# RCJ_OnStage2024_FC_pwr.net
KiCad netlist of a schematic drawn in Altium Designer
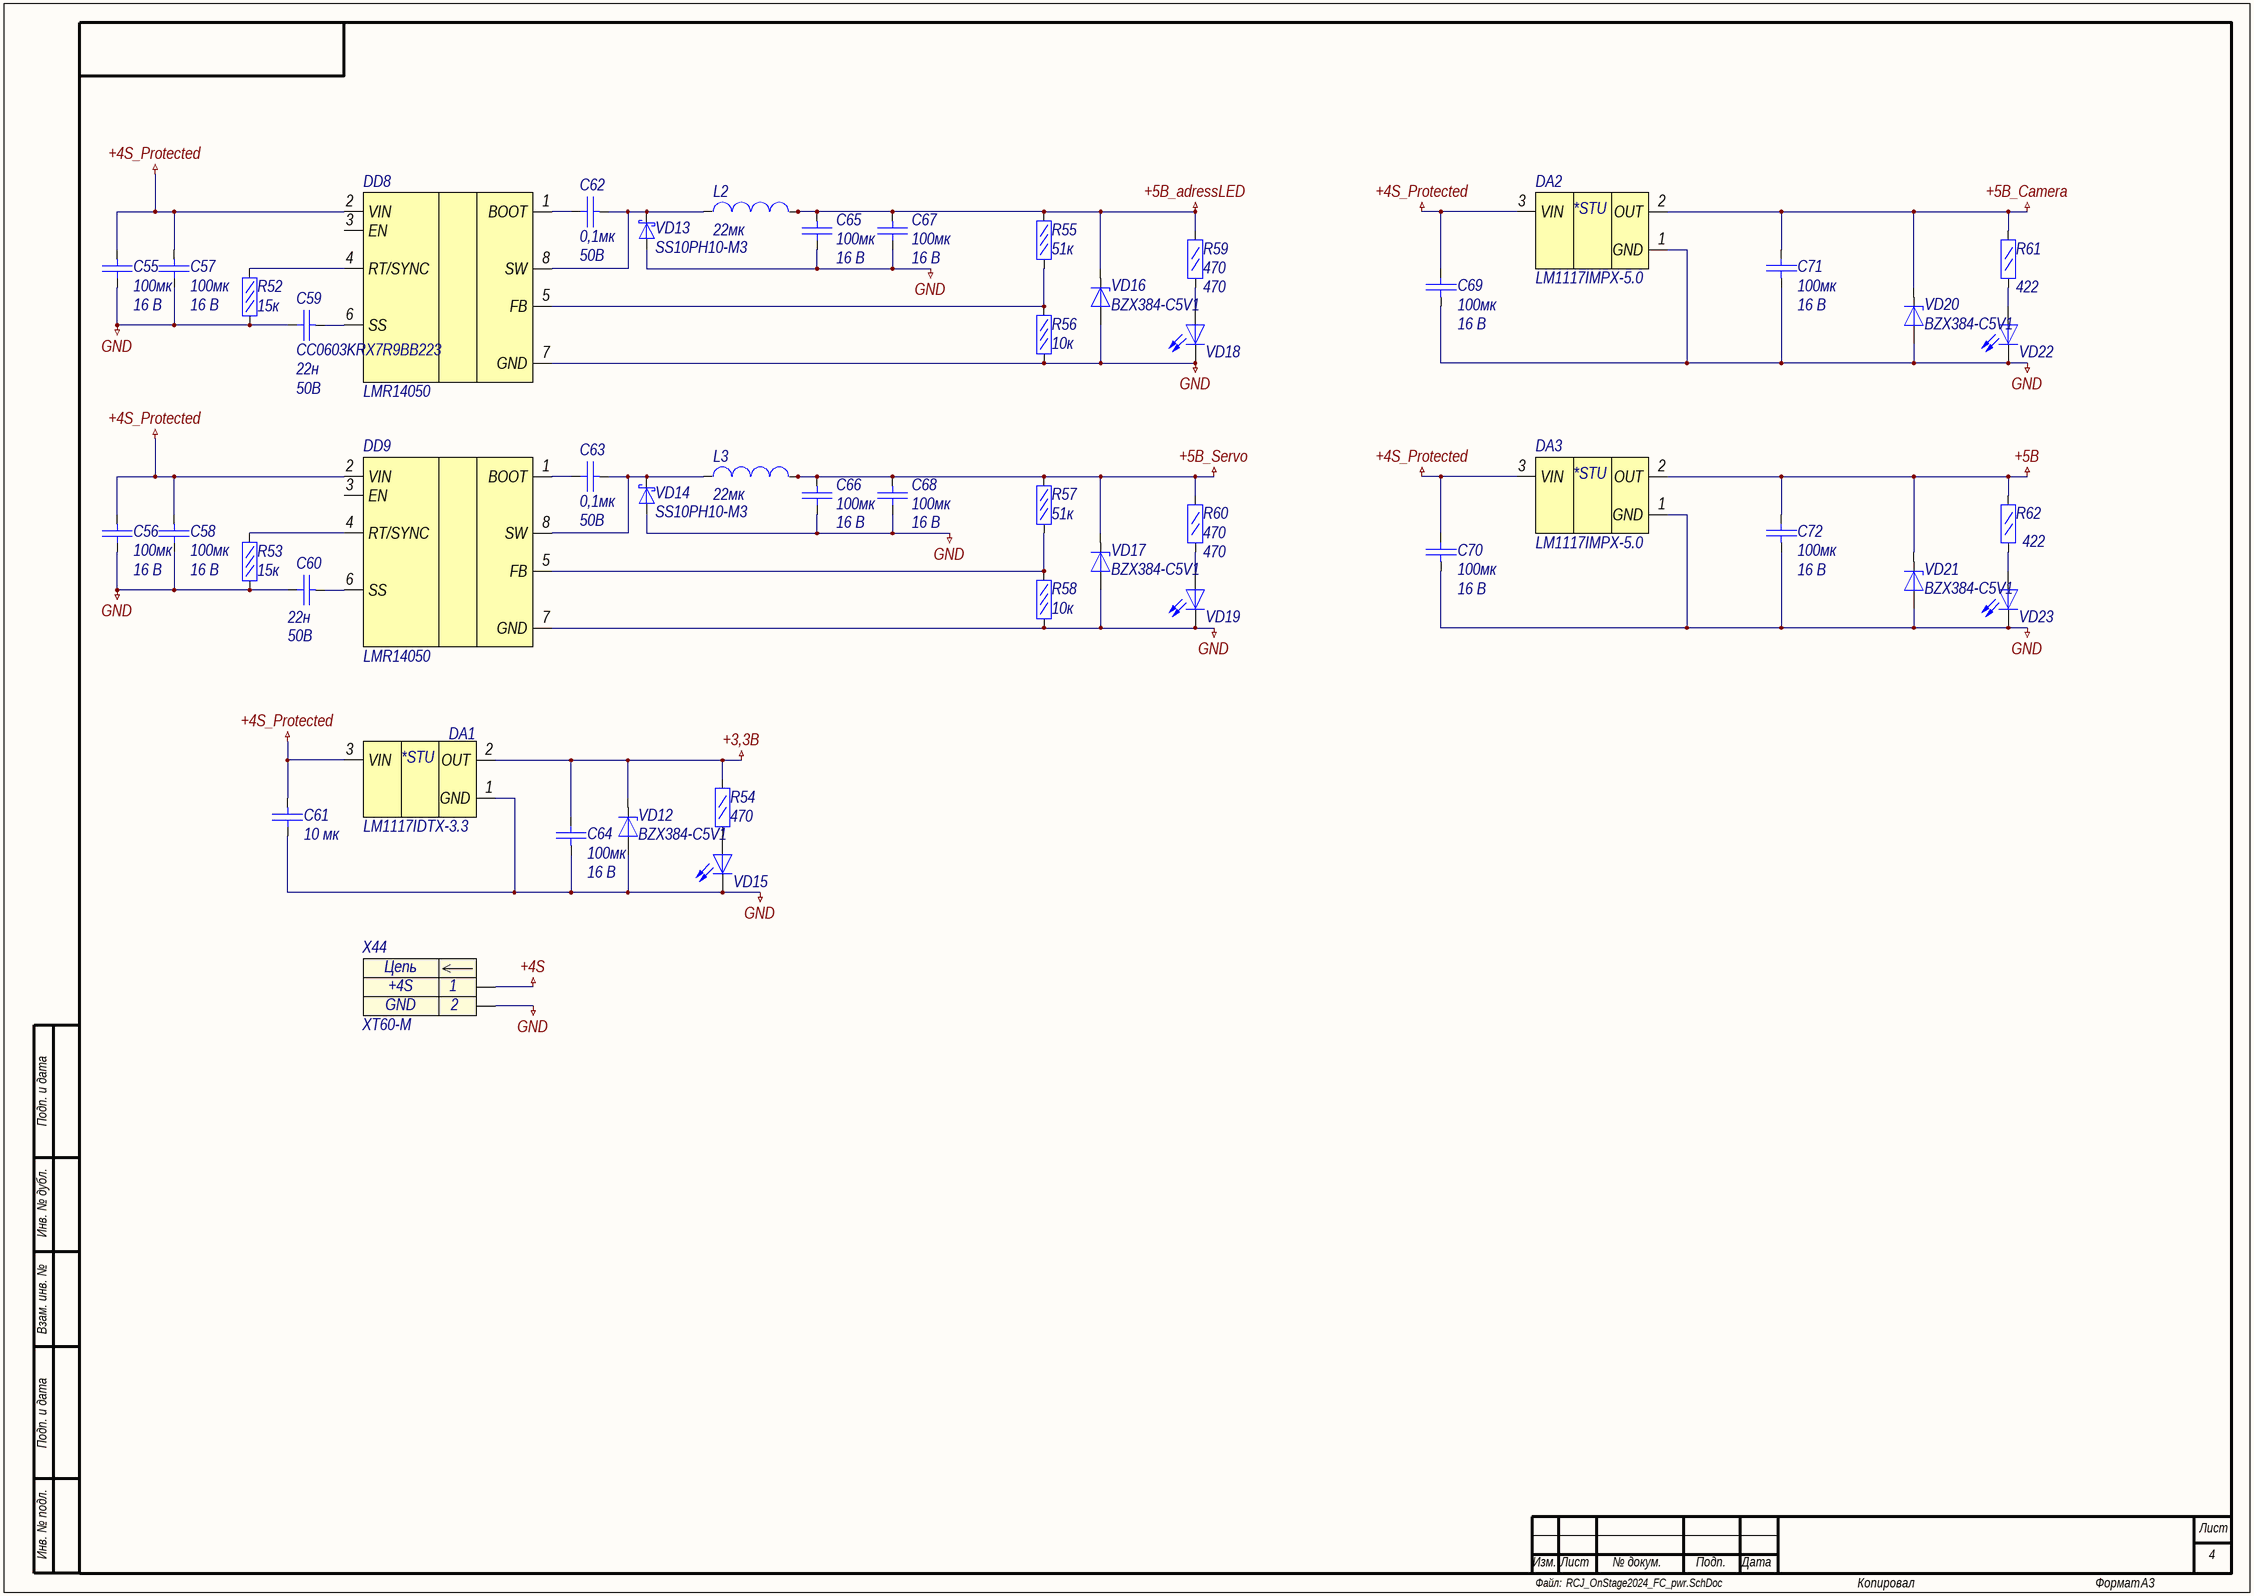
[diagram p0: RCJ_OnStage2024_FC_pwr.SchDoc]

(export (version "E")
  (design (tool "Eeschema 10.0.6"))
  (components
    (comp (ref "C55")
      (value "100мк")
      (footprint "C1210")
      (description "Конденсатор керамический 100мкФ 16В")
      (fields (field (name "VOLTAGE") "16 В"))
      (libsource (lib "capacitors") (part "CC1210MKX5R7BB107"))
    )
    (comp (ref "C56")
      (value "100мк")
      (footprint "C1210")
      (description "Конденсатор керамический 100мкФ 16В")
      (fields (field (name "VOLTAGE") "16 В"))
      (libsource (lib "capacitors") (part "CC1210MKX5R7BB107"))
    )
    (comp (ref "C57")
      (value "100мк")
      (footprint "C1210")
      (description "Конденсатор керамический 100мкФ 16В")
      (fields (field (name "VOLTAGE") "16 В"))
      (libsource (lib "capacitors") (part "CC1210MKX5R7BB107"))
    )
    (comp (ref "C58")
      (value "100мк")
      (footprint "C1210")
      (description "Конденсатор керамический 100мкФ 16В")
      (fields (field (name "VOLTAGE") "16 В"))
      (libsource (lib "capacitors") (part "CC1210MKX5R7BB107"))
    )
    (comp (ref "C59")
      (value "CC0603KRX7R9BB223")
      (footprint "C0603")
      (description "Конденсатор керамический 22нФ 50В")
      (fields (field (name "ALTIUM_VALUE") "22н") (field (name "VOLTAGE") "50В"))
      (libsource (lib "capacitors") (part "CC0603KRX7R9BB223"))
    )
    (comp (ref "C60")
      (value "22н")
      (footprint "C0603")
      (description "Конденсатор керамический 22нФ 50В")
      (fields (field (name "VOLTAGE") "50В") (field (name "Comment") "CC0603KRX7R9BB223"))
      (libsource (lib "capacitors") (part "CC0603KRX7R9BB223"))
    )
    (comp (ref "C61")
      (value "10 мк")
      (footprint "C0805")
      (description "Конденсатор кер. 10мкФ 25В")
      (libsource (lib "capacitors") (part "CC0805KKX5R8BB106"))
    )
    (comp (ref "C62")
      (value "0,1мк")
      (footprint "C0603")
      (description "Конденсатор кер. 0,1мкФ 50В X7R")
      (fields (field (name "MANUFACTURER") "Murata") (field (name "VOLTAGE") "50В"))
      (libsource (lib "capacitors") (part "GRM188R71H104KA93D"))
    )
    (comp (ref "C63")
      (value "0,1мк")
      (footprint "C0603")
      (description "Конденсатор кер. 0,1мкФ 50В X7R")
      (fields (field (name "MANUFACTURER") "Murata") (field (name "VOLTAGE") "50В"))
      (libsource (lib "capacitors") (part "GRM188R71H104KA93D"))
    )
    (comp (ref "C64")
      (value "100мк")
      (footprint "C1210")
      (description "Конденсатор керамический 100мкФ 16В")
      (fields (field (name "VOLTAGE") "16 В"))
      (libsource (lib "capacitors") (part "CC1210MKX5R7BB107"))
    )
    (comp (ref "C65")
      (value "100мк")
      (footprint "C1210")
      (description "Конденсатор керамический 100мкФ 16В")
      (fields (field (name "VOLTAGE") "16 В"))
      (libsource (lib "capacitors") (part "CC1210MKX5R7BB107"))
    )
    (comp (ref "C66")
      (value "100мк")
      (footprint "C1210")
      (description "Конденсатор керамический 100мкФ 16В")
      (fields (field (name "VOLTAGE") "16 В"))
      (libsource (lib "capacitors") (part "CC1210MKX5R7BB107"))
    )
    (comp (ref "C67")
      (value "100мк")
      (footprint "C1210")
      (description "Конденсатор керамический 100мкФ 16В")
      (fields (field (name "VOLTAGE") "16 В"))
      (libsource (lib "capacitors") (part "CC1210MKX5R7BB107"))
    )
    (comp (ref "C68")
      (value "100мк")
      (footprint "C1210")
      (description "Конденсатор керамический 100мкФ 16В")
      (fields (field (name "VOLTAGE") "16 В"))
      (libsource (lib "capacitors") (part "CC1210MKX5R7BB107"))
    )
    (comp (ref "C69")
      (value "100мк")
      (footprint "C1210")
      (description "Конденсатор керамический 100мкФ 16В")
      (fields (field (name "VOLTAGE") "16 В"))
      (libsource (lib "capacitors") (part "CC1210MKX5R7BB107"))
    )
    (comp (ref "C70")
      (value "100мк")
      (footprint "C1210")
      (description "Конденсатор керамический 100мкФ 16В")
      (fields (field (name "VOLTAGE") "16 В"))
      (libsource (lib "capacitors") (part "CC1210MKX5R7BB107"))
    )
    (comp (ref "C71")
      (value "100мк")
      (footprint "C1210")
      (description "Конденсатор керамический 100мкФ 16В")
      (fields (field (name "VOLTAGE") "16 В"))
      (libsource (lib "capacitors") (part "CC1210MKX5R7BB107"))
    )
    (comp (ref "C72")
      (value "100мк")
      (footprint "C1210")
      (description "Конденсатор керамический 100мкФ 16В")
      (fields (field (name "VOLTAGE") "16 В"))
      (libsource (lib "capacitors") (part "CC1210MKX5R7BB107"))
    )
    (comp (ref "DA1")
      (value "LM1117IDTX-3.3")
      (footprint "D-PAK")
      (description "Линейный стабилизатор напряжения 3,3В")
      (fields (field (name "MANUFACTURER") "Texas Instruments") (field (name "NAME") "LM1117IDTX-3.3"))
      (libsource (lib "power_supplies") (part "LM1117IDTX-3.3"))
    )
    (comp (ref "DA2")
      (value "LM1117IMPX-5.0")
      (footprint "SOT-223")
      (description "Линейный стабилизатор напряжения 5В")
      (libsource (lib "power_supplies") (part "LM1117IMPX-5.0"))
    )
    (comp (ref "DA3")
      (value "LM1117IMPX-5.0")
      (footprint "SOT-223")
      (description "Линейный стабилизатор напряжения 5В")
      (libsource (lib "power_supplies") (part "LM1117IMPX-5.0"))
    )
    (comp (ref "DD8")
      (value "LMR14050")
      (footprint "SO-8")
      (description "Стабилизатор напряжения 40 В 5 А")
      (libsource (lib "power_supplies") (part "LMR14050"))
    )
    (comp (ref "DD9")
      (value "LMR14050")
      (footprint "SO-8")
      (description "Стабилизатор напряжения 40 В 5 А")
      (libsource (lib "power_supplies") (part "LMR14050"))
    )
    (comp (ref "L2")
      (value "22мк")
      (footprint "SRP1038A")
      (description "Катушка индуктивности 22мкГн 5А")
      (fields (field (name "Comment") "SRP1038A-220M"))
      (libsource (lib "inductors") (part "SRP1038A-220M"))
    )
    (comp (ref "L3")
      (value "22мк")
      (footprint "SRP1038A")
      (description "Катушка индуктивности 22мкГн 5А")
      (fields (field (name "Comment") "SRP1038A-220M"))
      (libsource (lib "inductors") (part "SRP1038A-220M"))
    )
    (comp (ref "R52")
      (value "15к")
      (footprint "R0603")
      (description "Резистор 15кОм 0,063Вт 1%")
      (fields (field (name "MANUFACTURER") "YAGEO") (field (name "TOLERANCE") "1%"))
      (libsource (lib "resistors") (part "RC0603FR-0715KL"))
    )
    (comp (ref "R53")
      (value "15к")
      (footprint "R0603")
      (description "Резистор 15кОм 0,063Вт 1%")
      (fields (field (name "MANUFACTURER") "YAGEO") (field (name "TOLERANCE") "1%"))
      (libsource (lib "resistors") (part "RC0603FR-0715KL"))
    )
    (comp (ref "R54")
      (value "470")
      (footprint "R0805")
      (description "Резистор 470 0,125Вт 1%")
      (fields (field (name "MANUFACTURER") "YAGEO") (field (name "TOLERANCE") "1%"))
      (libsource (lib "resistors") (part "RC0805FR-07470RL"))
    )
    (comp (ref "R55")
      (value "51к")
      (footprint "R0603")
      (description "Резистор 51кОм 0.25Вт 5%")
      (libsource (lib "resistors") (part "RC1206FR-0751KL"))
    )
    (comp (ref "R56")
      (value "10к")
      (footprint "R0603")
      (description "Резистор 10кОм 0,063Вт 1%")
      (fields (field (name "MANUFACTURER") "YAGEO") (field (name "TOLERANCE") "1%"))
      (libsource (lib "resistors") (part "RC0603FR-0710KL"))
    )
    (comp (ref "R57")
      (value "51к")
      (footprint "R0603")
      (description "Резистор 51кОм 0.25Вт 5%")
      (libsource (lib "resistors") (part "RC1206FR-0751KL"))
    )
    (comp (ref "R58")
      (value "10к")
      (footprint "R0603")
      (description "Резистор 10кОм 0,063Вт 1%")
      (fields (field (name "MANUFACTURER") "YAGEO") (field (name "TOLERANCE") "1%"))
      (libsource (lib "resistors") (part "RC0603FR-0710KL"))
    )
    (comp (ref "R59")
      (value "470")
      (footprint "R0805")
      (description "Резистор 470 0,125Вт 1%")
      (fields
        (field (name "MANUFACTURER") "YAGEO")
        (field (name "TOLERANCE") "1%")
        (field (name "ALTIUM_VALUE") "470")
      )
      (libsource (lib "resistors") (part "RC0805FR-07470RL"))
    )
    (comp (ref "R60")
      (value "470")
      (footprint "R0805")
      (description "Резистор 470 0,125Вт 1%")
      (fields
        (field (name "MANUFACTURER") "YAGEO")
        (field (name "TOLERANCE") "1%")
        (field (name "ALTIUM_VALUE") "470")
      )
      (libsource (lib "resistors") (part "RC0805FR-07470RL"))
    )
    (comp (ref "R61")
      (value "422")
      (footprint "R0805")
      (description "Резистор 422 0,125Вт 1%")
      (fields (field (name "MANUFACTURER") "YAGEO") (field (name "TOLERANCE") "1%"))
      (libsource (lib "resistors") (part "RC0805FR-07422RL"))
    )
    (comp (ref "R62")
      (value "422")
      (footprint "R0805")
      (description "Резистор 422 0,125Вт 1%")
      (fields (field (name "MANUFACTURER") "YAGEO") (field (name "TOLERANCE") "1%"))
      (libsource (lib "resistors") (part "RC0805FR-07422RL"))
    )
    (comp (ref "VD12")
      (value "BZX384-C5V1")
      (footprint "SOD323")
      (description "Стабилитрон 5,1В")
      (libsource (lib "diodes") (part "BZX384-C5V1"))
    )
    (comp (ref "VD13")
      (value "SS10PH10-M3")
      (footprint "TO277A")
      (description "Диод Шоттки 86 А")
      (libsource (lib "diodes") (part "SS10PH10-M3/86A"))
    )
    (comp (ref "VD14")
      (value "SS10PH10-M3")
      (footprint "TO277A")
      (description "Диод Шоттки 86 А")
      (libsource (lib "diodes") (part "SS10PH10-M3/86A"))
    )
    (comp (ref "VD15")
      (value "~")
      (footprint "LED0603_RED")
      (description "Светодиод")
      (libsource (lib "diodes") (part "LED"))
    )
    (comp (ref "VD16")
      (value "BZX384-C5V1")
      (footprint "SOD323")
      (description "Стабилитрон 5,1В")
      (libsource (lib "diodes") (part "BZX384-C5V1"))
    )
    (comp (ref "VD17")
      (value "BZX384-C5V1")
      (footprint "SOD323")
      (description "Стабилитрон 5,1В")
      (libsource (lib "diodes") (part "BZX384-C5V1"))
    )
    (comp (ref "VD18")
      (value "~")
      (footprint "LED0603_RED")
      (description "Светодиод")
      (libsource (lib "diodes") (part "LED"))
    )
    (comp (ref "VD19")
      (value "~")
      (footprint "LED0603_RED")
      (description "Светодиод")
      (libsource (lib "diodes") (part "LED"))
    )
    (comp (ref "VD20")
      (value "BZX384-C5V1")
      (footprint "SOD323")
      (description "Стабилитрон 5,1В")
      (libsource (lib "diodes") (part "BZX384-C5V1"))
    )
    (comp (ref "VD21")
      (value "BZX384-C5V1")
      (footprint "SOD323")
      (description "Стабилитрон 5,1В")
      (libsource (lib "diodes") (part "BZX384-C5V1"))
    )
    (comp (ref "VD22")
      (value "~")
      (footprint "LED0603_RED")
      (description "Светодиод")
      (libsource (lib "diodes") (part "LED"))
    )
    (comp (ref "VD23")
      (value "~")
      (footprint "LED0603_RED")
      (description "Светодиод")
      (libsource (lib "diodes") (part "LED"))
    )
    (comp (ref "X44")
      (value "XT60-M")
      (footprint "XT60-M")
      (description "Разъем питания 2pin штекер")
      (libsource (lib "connectors") (part "XT60-M"))
    )
  )
  (nets
    (net (code "1") (name "+3,3В") (class "Default")
      (node (ref "C64") (pin "1") (pinfunction "1_1") (pintype "passive"))
      (node (ref "DA1") (pin "2") (pinfunction "OUT_2") (pintype "passive"))
      (node (ref "R54") (pin "2") (pinfunction "2_2") (pintype "passive"))
      (node (ref "VD12") (pin "2") (pinfunction "K_2") (pintype "passive"))
    )
    (net (code "2") (name "+4S") (class "Default")
      (node (ref "X44") (pin "1") (pinfunction "1_1") (pintype "passive"))
    )
    (net (code "3") (name "+4S_Protected") (class "Default")
      (node (ref "C55") (pin "2") (pinfunction "2_2") (pintype "passive"))
      (node (ref "C56") (pin "2") (pinfunction "2_2") (pintype "passive"))
      (node (ref "C57") (pin "2") (pinfunction "2_2") (pintype "passive"))
      (node (ref "C58") (pin "2") (pinfunction "2_2") (pintype "passive"))
      (node (ref "C61") (pin "2") (pinfunction "2_2") (pintype "passive"))
      (node (ref "C69") (pin "1") (pinfunction "1_1") (pintype "passive"))
      (node (ref "C70") (pin "1") (pinfunction "1_1") (pintype "passive"))
      (node (ref "DA1") (pin "3") (pinfunction "VIN_3") (pintype "passive"))
      (node (ref "DA2") (pin "3") (pinfunction "VIN_3") (pintype "passive"))
      (node (ref "DA3") (pin "3") (pinfunction "VIN_3") (pintype "passive"))
      (node (ref "DD8") (pin "2") (pinfunction "VIN_2") (pintype "passive"))
      (node (ref "DD9") (pin "2") (pinfunction "VIN_2") (pintype "passive"))
    )
    (net (code "4") (name "+5В") (class "Default")
      (node (ref "C72") (pin "1") (pinfunction "1_1") (pintype "passive"))
      (node (ref "DA3") (pin "2") (pinfunction "OUT_2") (pintype "passive"))
      (node (ref "R62") (pin "2") (pinfunction "2_2") (pintype "passive"))
      (node (ref "VD21") (pin "2") (pinfunction "K_2") (pintype "passive"))
    )
    (net (code "5") (name "+5В_Camera") (class "Default")
      (node (ref "C71") (pin "1") (pinfunction "1_1") (pintype "passive"))
      (node (ref "DA2") (pin "2") (pinfunction "OUT_2") (pintype "passive"))
      (node (ref "R61") (pin "2") (pinfunction "2_2") (pintype "passive"))
      (node (ref "VD20") (pin "2") (pinfunction "K_2") (pintype "passive"))
    )
    (net (code "6") (name "+5В_Servo") (class "Default")
      (node (ref "C66") (pin "2") (pinfunction "2_2") (pintype "passive"))
      (node (ref "C68") (pin "2") (pinfunction "2_2") (pintype "passive"))
      (node (ref "L3") (pin "2") (pinfunction "4_2") (pintype "passive"))
      (node (ref "R57") (pin "2") (pinfunction "2_2") (pintype "passive"))
      (node (ref "R60") (pin "2") (pinfunction "2_2") (pintype "passive"))
      (node (ref "VD17") (pin "2") (pinfunction "K_2") (pintype "passive"))
    )
    (net (code "7") (name "+5В_adressLED") (class "Default")
      (node (ref "C65") (pin "2") (pinfunction "2_2") (pintype "passive"))
      (node (ref "C67") (pin "2") (pinfunction "2_2") (pintype "passive"))
      (node (ref "L2") (pin "2") (pinfunction "4_2") (pintype "passive"))
      (node (ref "R55") (pin "2") (pinfunction "2_2") (pintype "passive"))
      (node (ref "R59") (pin "2") (pinfunction "2_2") (pintype "passive"))
      (node (ref "VD16") (pin "2") (pinfunction "K_2") (pintype "passive"))
    )
    (net (code "8") (name "GND") (class "Default")
      (node (ref "C55") (pin "1") (pinfunction "1_1") (pintype "passive"))
      (node (ref "C56") (pin "1") (pinfunction "1_1") (pintype "passive"))
      (node (ref "C57") (pin "1") (pinfunction "1_1") (pintype "passive"))
      (node (ref "C58") (pin "1") (pinfunction "1_1") (pintype "passive"))
      (node (ref "C59") (pin "1") (pinfunction "1_1") (pintype "passive"))
      (node (ref "C60") (pin "1") (pinfunction "1_1") (pintype "passive"))
      (node (ref "C61") (pin "1") (pinfunction "1_1") (pintype "passive"))
      (node (ref "C64") (pin "2") (pinfunction "2_2") (pintype "passive"))
      (node (ref "C65") (pin "1") (pinfunction "1_1") (pintype "passive"))
      (node (ref "C66") (pin "1") (pinfunction "1_1") (pintype "passive"))
      (node (ref "C67") (pin "1") (pinfunction "1_1") (pintype "passive"))
      (node (ref "C68") (pin "1") (pinfunction "1_1") (pintype "passive"))
      (node (ref "C69") (pin "2") (pinfunction "2_2") (pintype "passive"))
      (node (ref "C70") (pin "2") (pinfunction "2_2") (pintype "passive"))
      (node (ref "C71") (pin "2") (pinfunction "2_2") (pintype "passive"))
      (node (ref "C72") (pin "2") (pinfunction "2_2") (pintype "passive"))
      (node (ref "DA1") (pin "1") (pinfunction "GND_1") (pintype "passive"))
      (node (ref "DA2") (pin "1") (pinfunction "GND_1") (pintype "passive"))
      (node (ref "DA3") (pin "1") (pinfunction "GND_1") (pintype "passive"))
      (node (ref "DD8") (pin "7") (pinfunction "GND_7") (pintype "passive"))
      (node (ref "DD9") (pin "7") (pinfunction "GND_7") (pintype "passive"))
      (node (ref "R52") (pin "1") (pinfunction "1_1") (pintype "passive"))
      (node (ref "R53") (pin "1") (pinfunction "1_1") (pintype "passive"))
      (node (ref "R56") (pin "1") (pinfunction "1_1") (pintype "passive"))
      (node (ref "R58") (pin "1") (pinfunction "1_1") (pintype "passive"))
      (node (ref "VD12") (pin "1") (pinfunction "A_1") (pintype "passive"))
      (node (ref "VD13") (pin "2") (pinfunction "A_2") (pintype "passive"))
      (node (ref "VD14") (pin "2") (pinfunction "A_2") (pintype "passive"))
      (node (ref "VD15") (pin "1") (pinfunction "K_1") (pintype "passive"))
      (node (ref "VD16") (pin "1") (pinfunction "A_1") (pintype "passive"))
      (node (ref "VD17") (pin "1") (pinfunction "A_1") (pintype "passive"))
      (node (ref "VD18") (pin "1") (pinfunction "K_1") (pintype "passive"))
      (node (ref "VD19") (pin "1") (pinfunction "K_1") (pintype "passive"))
      (node (ref "VD20") (pin "1") (pinfunction "A_1") (pintype "passive"))
      (node (ref "VD21") (pin "1") (pinfunction "A_1") (pintype "passive"))
      (node (ref "VD22") (pin "1") (pinfunction "K_1") (pintype "passive"))
      (node (ref "VD23") (pin "1") (pinfunction "K_1") (pintype "passive"))
      (node (ref "X44") (pin "2") (pinfunction "2_2") (pintype "passive"))
    )
    (net (code "9") (name "Net-(DD8-BOOT)") (class "Default")
      (node (ref "C62") (pin "1") (pinfunction "1_1") (pintype "passive"))
      (node (ref "DD8") (pin "1") (pinfunction "BOOT_1") (pintype "passive"))
    )
    (net (code "10") (name "Net-(DD8-FB)") (class "Default")
      (node (ref "DD8") (pin "5") (pinfunction "FB_5") (pintype "passive"))
      (node (ref "R55") (pin "1") (pinfunction "1_1") (pintype "passive"))
      (node (ref "R56") (pin "2") (pinfunction "2_2") (pintype "passive"))
    )
    (net (code "11") (name "Net-(DD8-RT{slash}SYNC)") (class "Default")
      (node (ref "DD8") (pin "4") (pinfunction "RT/SYNC_4") (pintype "passive"))
      (node (ref "R52") (pin "2") (pinfunction "2_2") (pintype "passive"))
    )
    (net (code "12") (name "Net-(DD8-SS)") (class "Default")
      (node (ref "C59") (pin "2") (pinfunction "2_2") (pintype "passive"))
      (node (ref "DD8") (pin "6") (pinfunction "SS_6") (pintype "passive"))
    )
    (net (code "13") (name "Net-(DD8-SW)") (class "Default")
      (node (ref "C62") (pin "2") (pinfunction "2_2") (pintype "passive"))
      (node (ref "DD8") (pin "8") (pinfunction "SW_8") (pintype "passive"))
      (node (ref "L2") (pin "1") (pinfunction "3_1") (pintype "passive"))
      (node (ref "VD13") (pin "1") (pinfunction "K_1") (pintype "passive"))
    )
    (net (code "14") (name "Net-(DD9-BOOT)") (class "Default")
      (node (ref "C63") (pin "1") (pinfunction "1_1") (pintype "passive"))
      (node (ref "DD9") (pin "1") (pinfunction "BOOT_1") (pintype "passive"))
    )
    (net (code "15") (name "Net-(DD9-FB)") (class "Default")
      (node (ref "DD9") (pin "5") (pinfunction "FB_5") (pintype "passive"))
      (node (ref "R57") (pin "1") (pinfunction "1_1") (pintype "passive"))
      (node (ref "R58") (pin "2") (pinfunction "2_2") (pintype "passive"))
    )
    (net (code "16") (name "Net-(DD9-RT{slash}SYNC)") (class "Default")
      (node (ref "DD9") (pin "4") (pinfunction "RT/SYNC_4") (pintype "passive"))
      (node (ref "R53") (pin "2") (pinfunction "2_2") (pintype "passive"))
    )
    (net (code "17") (name "Net-(DD9-SS)") (class "Default")
      (node (ref "C60") (pin "2") (pinfunction "2_2") (pintype "passive"))
      (node (ref "DD9") (pin "6") (pinfunction "SS_6") (pintype "passive"))
    )
    (net (code "18") (name "Net-(DD9-SW)") (class "Default")
      (node (ref "C63") (pin "2") (pinfunction "2_2") (pintype "passive"))
      (node (ref "DD9") (pin "8") (pinfunction "SW_8") (pintype "passive"))
      (node (ref "L3") (pin "1") (pinfunction "3_1") (pintype "passive"))
      (node (ref "VD14") (pin "1") (pinfunction "K_1") (pintype "passive"))
    )
    (net (code "19") (name "Net-(VD15-A)") (class "Default")
      (node (ref "R54") (pin "1") (pinfunction "1_1") (pintype "passive"))
      (node (ref "VD15") (pin "2") (pinfunction "A_2") (pintype "passive"))
    )
    (net (code "20") (name "Net-(VD18-A)") (class "Default")
      (node (ref "R59") (pin "1") (pinfunction "1_1") (pintype "passive"))
      (node (ref "VD18") (pin "2") (pinfunction "A_2") (pintype "passive"))
    )
    (net (code "21") (name "Net-(VD19-A)") (class "Default")
      (node (ref "R60") (pin "1") (pinfunction "1_1") (pintype "passive"))
      (node (ref "VD19") (pin "2") (pinfunction "A_2") (pintype "passive"))
    )
    (net (code "22") (name "Net-(VD22-A)") (class "Default")
      (node (ref "R61") (pin "1") (pinfunction "1_1") (pintype "passive"))
      (node (ref "VD22") (pin "2") (pinfunction "A_2") (pintype "passive"))
    )
    (net (code "23") (name "Net-(VD23-A)") (class "Default")
      (node (ref "R62") (pin "1") (pinfunction "1_1") (pintype "passive"))
      (node (ref "VD23") (pin "2") (pinfunction "A_2") (pintype "passive"))
    )
    (net (code "24") (name "unconnected-(DD8-EN-Pad3)") (class "Default")
      (node (ref "DD8") (pin "3") (pinfunction "EN_3") (pintype "passive"))
    )
    (net (code "25") (name "unconnected-(DD9-EN-Pad3)") (class "Default")
      (node (ref "DD9") (pin "3") (pinfunction "EN_3") (pintype "passive"))
    )
  )
)
